# TDA2030_2_1.net
KiCad netlist of a schematic drawn in Altium Designer
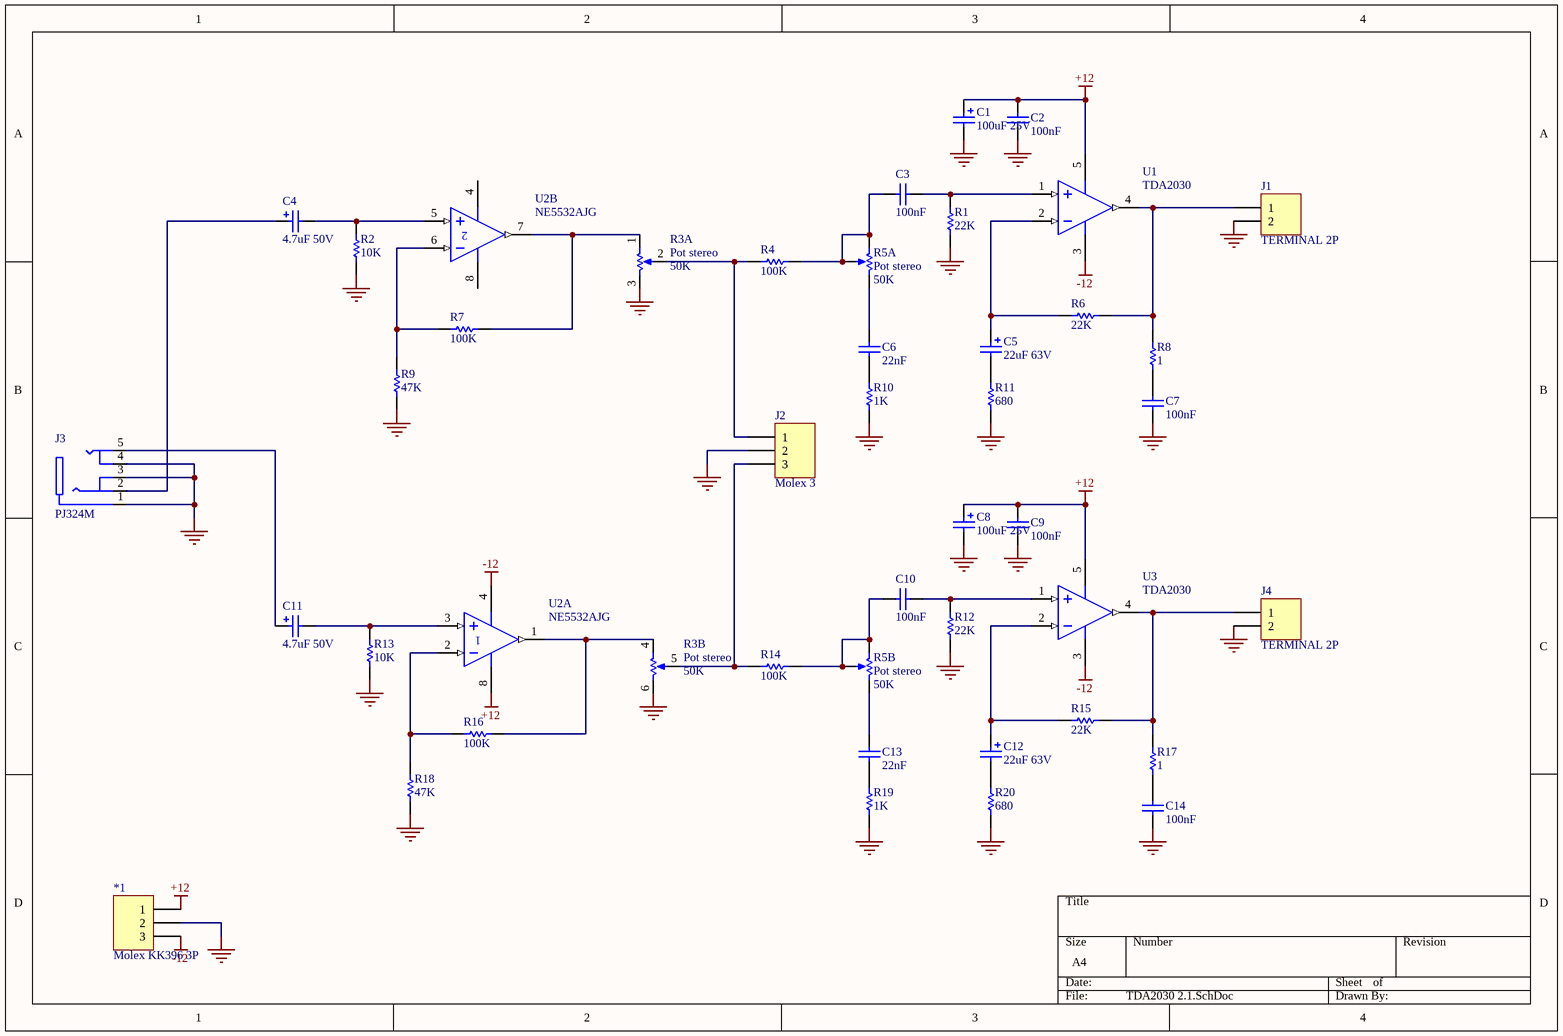
[diagram p0: TDA2030 2.1.SchDoc]

(export (version "E")
  (design (tool "Eeschema 10.0.6"))
  (components
    (comp (ref "*1")
      (value "Molex KK396 3P")
      (footprint "Molex kk396 3P")
      (libsource (lib "Schlib") (part "Molex KK396 3P"))
    )
    (comp (ref "C1")
      (value "100uF 25V")
      (footprint "100uF 25V")
      (description "Polarized Capacitor (Radial)")
      (fields (field (name "PUBLISHER") "Altium Limited"))
      (libsource (lib "Schlib") (part "100uF 25V"))
    )
    (comp (ref "C2")
      (value "100nF")
      (footprint "104")
      (description "Capacitor")
      (fields (field (name "PUBLISHER") "Altium Limited"))
      (libsource (lib "Schlib") (part "104"))
    )
    (comp (ref "C3")
      (value "100nF")
      (footprint "104")
      (description "Capacitor")
      (fields (field (name "PUBLISHER") "Altium Limited"))
      (libsource (lib "Schlib") (part "104"))
    )
    (comp (ref "C4")
      (value "4.7uF 50V")
      (footprint "4.7uF 50V")
      (description "Polarized Capacitor (Radial)")
      (fields (field (name "PUBLISHER") "Altium Limited"))
      (libsource (lib "Schlib") (part "4.7uF 50V"))
    )
    (comp (ref "C5")
      (value "22uF 63V")
      (footprint "22uF 63V")
      (description "Polarized Capacitor (Radial)")
      (fields (field (name "PUBLISHER") "Altium Limited"))
      (libsource (lib "Schlib") (part "22uF 63V"))
    )
    (comp (ref "C6")
      (value "22nF")
      (footprint "104")
      (description "Capacitor")
      (fields (field (name "PUBLISHER") "Altium Limited"))
      (libsource (lib "Schlib") (part "223"))
    )
    (comp (ref "C7")
      (value "100nF")
      (footprint "104")
      (description "Capacitor")
      (fields (field (name "PUBLISHER") "Altium Limited"))
      (libsource (lib "Schlib") (part "104"))
    )
    (comp (ref "C8")
      (value "100uF 25V")
      (footprint "100uF 25V")
      (description "Polarized Capacitor (Radial)")
      (fields (field (name "PUBLISHER") "Altium Limited"))
      (libsource (lib "Schlib") (part "100uF 25V"))
    )
    (comp (ref "C9")
      (value "100nF")
      (footprint "104")
      (description "Capacitor")
      (fields (field (name "PUBLISHER") "Altium Limited"))
      (libsource (lib "Schlib") (part "104"))
    )
    (comp (ref "C10")
      (value "100nF")
      (footprint "104")
      (description "Capacitor")
      (fields (field (name "PUBLISHER") "Altium Limited"))
      (libsource (lib "Schlib") (part "104"))
    )
    (comp (ref "C11")
      (value "4.7uF 50V")
      (footprint "4.7uF 50V")
      (description "Polarized Capacitor (Radial)")
      (fields (field (name "PUBLISHER") "Altium Limited"))
      (libsource (lib "Schlib") (part "4.7uF 50V"))
    )
    (comp (ref "C12")
      (value "22uF 63V")
      (footprint "22uF 63V")
      (description "Polarized Capacitor (Radial)")
      (fields (field (name "PUBLISHER") "Altium Limited"))
      (libsource (lib "Schlib") (part "22uF 63V"))
    )
    (comp (ref "C13")
      (value "22nF")
      (footprint "104")
      (description "Capacitor")
      (fields (field (name "PUBLISHER") "Altium Limited"))
      (libsource (lib "Schlib") (part "223"))
    )
    (comp (ref "C14")
      (value "100nF")
      (footprint "104")
      (description "Capacitor")
      (fields (field (name "PUBLISHER") "Altium Limited"))
      (libsource (lib "Schlib") (part "104"))
    )
    (comp (ref "J1")
      (value "TERMINAL 2P")
      (footprint "TERMINAL 2P")
      (description "Header, 2-Pin")
      (fields (field (name "PUBLISHER") "Altium Limited"))
      (libsource (lib "Schlib") (part "TERMINAL 2P"))
    )
    (comp (ref "J2")
      (value "Molex 3")
      (footprint "Molex kk100 3P")
      (description "Header, 3-Pin")
      (fields (field (name "PUBLISHER") "Altium Limited"))
      (libsource (lib "Schlib") (part "Molex kk100 3P"))
    )
    (comp (ref "J3")
      (value "PJ324M")
      (footprint "WENZHOU_PJ324M")
      (description "Headphone Stereo jack/Audio connector")
      (fields (field (name "MF") "Wenzhou QingPu Electronics Co.Ltd"))
      (libsource (lib "Schlib") (part "PJ324M"))
    )
    (comp (ref "J4")
      (value "TERMINAL 2P")
      (footprint "TERMINAL 2P")
      (description "Header, 2-Pin")
      (fields (field (name "PUBLISHER") "Altium Limited"))
      (libsource (lib "Schlib") (part "TERMINAL 2P"))
    )
    (comp (ref "R1")
      (value "22K")
      (footprint "AXIAL-0.4")
      (description "Resistor")
      (fields (field (name "PUBLISHER") "Altium Limited"))
      (libsource (lib "Miscellaneous Devices") (part "Res1"))
    )
    (comp (ref "R2")
      (value "10K")
      (footprint "AXIAL-0.4")
      (description "Resistor")
      (fields (field (name "PUBLISHER") "Altium Limited"))
      (libsource (lib "Miscellaneous Devices") (part "Res1"))
    )
    (comp (ref "R3")
      (value "Pot stereo")
      (footprint "Pote doble")
      (description "Potentiometer")
      (fields (field (name "ALTIUM_VALUE") "50K") (field (name "PUBLISHER") "Altium Limited"))
      (libsource (lib "") (part "RPot_1"))
    )
    (comp (ref "R4")
      (value "100K")
      (footprint "AXIAL-0.4")
      (description "Resistor")
      (fields (field (name "PUBLISHER") "Altium Limited"))
      (libsource (lib "Miscellaneous Devices") (part "Res1"))
    )
    (comp (ref "R5")
      (value "Pot stereo")
      (footprint "Pote doble")
      (description "Potentiometer")
      (fields (field (name "ALTIUM_VALUE") "50K") (field (name "PUBLISHER") "Altium Limited"))
      (libsource (lib "Schlib") (part "RPot"))
    )
    (comp (ref "R6")
      (value "22K")
      (footprint "AXIAL-0.4")
      (description "Resistor")
      (fields (field (name "PUBLISHER") "Altium Limited"))
      (libsource (lib "Miscellaneous Devices") (part "Res1"))
    )
    (comp (ref "R7")
      (value "100K")
      (footprint "AXIAL-0.4")
      (description "Resistor")
      (fields (field (name "PUBLISHER") "Altium Limited"))
      (libsource (lib "Miscellaneous Devices") (part "Res1"))
    )
    (comp (ref "R8")
      (value "1")
      (footprint "AXIAL-0.4")
      (description "Resistor")
      (fields (field (name "PUBLISHER") "Altium Limited"))
      (libsource (lib "Miscellaneous Devices") (part "Res1"))
    )
    (comp (ref "R9")
      (value "47K")
      (footprint "AXIAL-0.4")
      (description "Resistor")
      (fields (field (name "PUBLISHER") "Altium Limited"))
      (libsource (lib "Miscellaneous Devices") (part "Res1"))
    )
    (comp (ref "R10")
      (value "1K")
      (footprint "AXIAL-0.4")
      (description "Resistor")
      (fields (field (name "PUBLISHER") "Altium Limited"))
      (libsource (lib "Miscellaneous Devices") (part "Res1"))
    )
    (comp (ref "R11")
      (value "680")
      (footprint "AXIAL-0.4")
      (description "Resistor")
      (fields (field (name "PUBLISHER") "Altium Limited"))
      (libsource (lib "Miscellaneous Devices") (part "Res1"))
    )
    (comp (ref "R12")
      (value "22K")
      (footprint "AXIAL-0.4")
      (description "Resistor")
      (fields (field (name "PUBLISHER") "Altium Limited"))
      (libsource (lib "Miscellaneous Devices") (part "Res1"))
    )
    (comp (ref "R13")
      (value "10K")
      (footprint "AXIAL-0.4")
      (description "Resistor")
      (fields (field (name "PUBLISHER") "Altium Limited"))
      (libsource (lib "Miscellaneous Devices") (part "Res1"))
    )
    (comp (ref "R14")
      (value "100K")
      (footprint "AXIAL-0.4")
      (description "Resistor")
      (fields (field (name "PUBLISHER") "Altium Limited"))
      (libsource (lib "Miscellaneous Devices") (part "Res1"))
    )
    (comp (ref "R15")
      (value "22K")
      (footprint "AXIAL-0.4")
      (description "Resistor")
      (fields (field (name "PUBLISHER") "Altium Limited"))
      (libsource (lib "Miscellaneous Devices") (part "Res1"))
    )
    (comp (ref "R16")
      (value "100K")
      (footprint "AXIAL-0.4")
      (description "Resistor")
      (fields (field (name "PUBLISHER") "Altium Limited"))
      (libsource (lib "Miscellaneous Devices") (part "Res1"))
    )
    (comp (ref "R17")
      (value "1")
      (footprint "AXIAL-0.4")
      (description "Resistor")
      (fields (field (name "PUBLISHER") "Altium Limited"))
      (libsource (lib "Miscellaneous Devices") (part "Res1"))
    )
    (comp (ref "R18")
      (value "47K")
      (footprint "AXIAL-0.4")
      (description "Resistor")
      (fields (field (name "PUBLISHER") "Altium Limited"))
      (libsource (lib "Miscellaneous Devices") (part "Res1"))
    )
    (comp (ref "R19")
      (value "1K")
      (footprint "AXIAL-0.4 MIA")
      (description "Resistor")
      (fields (field (name "PUBLISHER") "Altium Limited"))
      (libsource (lib "Miscellaneous Devices") (part "Res1"))
    )
    (comp (ref "R20")
      (value "680")
      (footprint "AXIAL-0.4")
      (description "Resistor")
      (fields (field (name "PUBLISHER") "Altium Limited"))
      (libsource (lib "Miscellaneous Devices") (part "Res1"))
    )
    (comp (ref "U1") (value "TDA2030") (footprint "TDA2030") (libsource (lib "Schlib") (part "TDA2030")))
    (comp (ref "U2")
      (value "NE5532AJG")
      (footprint "DIP-8")
      (description "Dual Low-Noise Operational Amplifier")
      (fields (field (name "PUBLISHER") "Altium Limited"))
      (libsource (lib "TI Operational Amplifier") (part "NE5532AJG"))
    )
    (comp (ref "U3") (value "TDA2030") (footprint "TDA2030") (libsource (lib "Schlib") (part "TDA2030")))
  )
  (nets
    (net (code "1") (name "+12") (class "Default")
      (node (ref "*1") (pin "1") (pinfunction "1_1") (pintype "passive"))
      (node (ref "C1") (pin "1") (pinfunction "1_1") (pintype "passive"))
      (node (ref "C2") (pin "2") (pinfunction "2_2") (pintype "passive"))
      (node (ref "C8") (pin "1") (pinfunction "1_1") (pintype "passive"))
      (node (ref "C9") (pin "1") (pinfunction "1_1") (pintype "passive"))
      (node (ref "U1") (pin "5") (pinfunction "V+_5") (pintype "power_in"))
      (node (ref "U2") (pin "8") (pinfunction "V+_8") (pintype "power_in"))
      (node (ref "U3") (pin "5") (pinfunction "V+_5") (pintype "power_in"))
    )
    (net (code "2") (name "-12") (class "Default")
      (node (ref "*1") (pin "3") (pinfunction "3_3") (pintype "passive"))
      (node (ref "U1") (pin "3") (pinfunction "V-_3") (pintype "power_in"))
      (node (ref "U2") (pin "4") (pinfunction "V-_4") (pintype "power_in"))
      (node (ref "U3") (pin "3") (pinfunction "V-_3") (pintype "power_in"))
    )
    (net (code "3") (name "GND") (class "Default")
      (node (ref "*1") (pin "2") (pinfunction "2_2") (pintype "passive"))
      (node (ref "C1") (pin "2") (pinfunction "2_2") (pintype "passive"))
      (node (ref "C14") (pin "2") (pinfunction "2_2") (pintype "passive"))
      (node (ref "C2") (pin "1") (pinfunction "1_1") (pintype "passive"))
      (node (ref "C7") (pin "2") (pinfunction "2_2") (pintype "passive"))
      (node (ref "C8") (pin "2") (pinfunction "2_2") (pintype "passive"))
      (node (ref "C9") (pin "2") (pinfunction "2_2") (pintype "passive"))
      (node (ref "J1") (pin "2") (pinfunction "2_2") (pintype "passive"))
      (node (ref "J2") (pin "2") (pinfunction "2_2") (pintype "passive"))
      (node (ref "J3") (pin "1") (pinfunction "SLEEVE_1") (pintype "passive"))
      (node (ref "J3") (pin "3") (pinfunction "RING_2_3") (pintype "passive"))
      (node (ref "J3") (pin "4") (pinfunction "TIP_1_4") (pintype "passive"))
      (node (ref "J4") (pin "2") (pinfunction "2_2") (pintype "passive"))
      (node (ref "R1") (pin "1") (pinfunction "1_1") (pintype "passive"))
      (node (ref "R10") (pin "2") (pinfunction "2_2") (pintype "passive"))
      (node (ref "R11") (pin "1") (pinfunction "1_1") (pintype "passive"))
      (node (ref "R12") (pin "1") (pinfunction "1_1") (pintype "passive"))
      (node (ref "R13") (pin "2") (pinfunction "2_2") (pintype "passive"))
      (node (ref "R18") (pin "2") (pinfunction "2_2") (pintype "passive"))
      (node (ref "R19") (pin "2") (pinfunction "2_2") (pintype "passive"))
      (node (ref "R2") (pin "2") (pinfunction "2_2") (pintype "passive"))
      (node (ref "R20") (pin "1") (pinfunction "1_1") (pintype "passive"))
      (node (ref "R3") (pin "3") (pinfunction "BOT_3") (pintype "passive"))
      (node (ref "R3") (pin "6") (pinfunction "BOT_6") (pintype "passive"))
      (node (ref "R9") (pin "2") (pinfunction "2_2") (pintype "passive"))
    )
    (net (code "4") (name "Net-(C5-Pad2)") (class "Default")
      (node (ref "C5") (pin "2") (pinfunction "2_2") (pintype "passive"))
      (node (ref "R11") (pin "2") (pinfunction "2_2") (pintype "passive"))
    )
    (net (code "5") (name "Net-(C6-Pad1)") (class "Default")
      (node (ref "C6") (pin "1") (pinfunction "1_1") (pintype "passive"))
      (node (ref "R10") (pin "1") (pinfunction "1_1") (pintype "passive"))
    )
    (net (code "6") (name "Net-(C7-Pad1)") (class "Default")
      (node (ref "C7") (pin "1") (pinfunction "1_1") (pintype "passive"))
      (node (ref "R8") (pin "2") (pinfunction "2_2") (pintype "passive"))
    )
    (net (code "7") (name "Net-(C12-Pad2)") (class "Default")
      (node (ref "C12") (pin "2") (pinfunction "2_2") (pintype "passive"))
      (node (ref "R20") (pin "2") (pinfunction "2_2") (pintype "passive"))
    )
    (net (code "8") (name "Net-(C13-Pad1)") (class "Default")
      (node (ref "C13") (pin "1") (pinfunction "1_1") (pintype "passive"))
      (node (ref "R19") (pin "1") (pinfunction "1_1") (pintype "passive"))
    )
    (net (code "9") (name "Net-(C14-Pad1)") (class "Default")
      (node (ref "C14") (pin "1") (pinfunction "1_1") (pintype "passive"))
      (node (ref "R17") (pin "2") (pinfunction "2_2") (pintype "passive"))
    )
    (net (code "10") (name "Net-(J3-RING_1)") (class "Default")
      (node (ref "C4") (pin "1") (pinfunction "1_1") (pintype "passive"))
      (node (ref "J3") (pin "2") (pinfunction "RING_1_2") (pintype "passive"))
    )
    (net (code "11") (name "Net-(J3-TIP_2)") (class "Default")
      (node (ref "C11") (pin "1") (pinfunction "1_1") (pintype "passive"))
      (node (ref "J3") (pin "5") (pinfunction "TIP_2_5") (pintype "passive"))
    )
    (net (code "12") (name "Net-(R3A-TAP)") (class "Default")
      (node (ref "J2") (pin "1") (pinfunction "1_1") (pintype "passive"))
      (node (ref "R3") (pin "2") (pinfunction "TAP_2") (pintype "passive"))
      (node (ref "R4") (pin "2") (pinfunction "2_2") (pintype "passive"))
    )
    (net (code "13") (name "Net-(R3A-TOP)") (class "Default")
      (node (ref "R3") (pin "1") (pinfunction "TOP_1") (pintype "passive"))
      (node (ref "R7") (pin "1") (pinfunction "1_1") (pintype "passive"))
      (node (ref "U2") (pin "7") (pinfunction "OUT_7") (pintype "output"))
    )
    (net (code "14") (name "Net-(R3B-TAP)") (class "Default")
      (node (ref "J2") (pin "3") (pinfunction "3_3") (pintype "passive"))
      (node (ref "R14") (pin "2") (pinfunction "2_2") (pintype "passive"))
      (node (ref "R3") (pin "5") (pinfunction "TAP_5") (pintype "passive"))
    )
    (net (code "15") (name "Net-(R3B-TOP)") (class "Default")
      (node (ref "R16") (pin "1") (pinfunction "1_1") (pintype "passive"))
      (node (ref "R3") (pin "4") (pinfunction "TOP_4") (pintype "passive"))
      (node (ref "U2") (pin "1") (pinfunction "OUT_1") (pintype "output"))
    )
    (net (code "16") (name "Net-(R5A-BOT)") (class "Default")
      (node (ref "C3") (pin "2") (pinfunction "2_2") (pintype "passive"))
      (node (ref "R4") (pin "1") (pinfunction "1_1") (pintype "passive"))
      (node (ref "R5") (pin "2") (pinfunction "TAP_2") (pintype "passive"))
      (node (ref "R5") (pin "3") (pinfunction "BOT_3") (pintype "passive"))
    )
    (net (code "17") (name "Net-(R5A-TOP)") (class "Default")
      (node (ref "C6") (pin "2") (pinfunction "2_2") (pintype "passive"))
      (node (ref "R5") (pin "1") (pinfunction "TOP_1") (pintype "passive"))
    )
    (net (code "18") (name "Net-(R5B-BOT)") (class "Default")
      (node (ref "C10") (pin "2") (pinfunction "2_2") (pintype "passive"))
      (node (ref "R14") (pin "1") (pinfunction "1_1") (pintype "passive"))
      (node (ref "R5") (pin "5") (pinfunction "TAP_5") (pintype "passive"))
      (node (ref "R5") (pin "6") (pinfunction "BOT_6") (pintype "passive"))
    )
    (net (code "19") (name "Net-(R5B-TOP)") (class "Default")
      (node (ref "C13") (pin "2") (pinfunction "2_2") (pintype "passive"))
      (node (ref "R5") (pin "4") (pinfunction "TOP_4") (pintype "passive"))
    )
    (net (code "20") (name "Net-(U1-IN+)") (class "Default")
      (node (ref "C3") (pin "1") (pinfunction "1_1") (pintype "passive"))
      (node (ref "R1") (pin "2") (pinfunction "2_2") (pintype "passive"))
      (node (ref "U1") (pin "1") (pinfunction "IN+_1") (pintype "input"))
    )
    (net (code "21") (name "Net-(U1-IN-)") (class "Default")
      (node (ref "C5") (pin "1") (pinfunction "1_1") (pintype "passive"))
      (node (ref "R6") (pin "2") (pinfunction "2_2") (pintype "passive"))
      (node (ref "U1") (pin "2") (pinfunction "IN-_2") (pintype "input"))
    )
    (net (code "22") (name "Net-(U1-OUT)") (class "Default")
      (node (ref "J1") (pin "1") (pinfunction "1_1") (pintype "passive"))
      (node (ref "R6") (pin "1") (pinfunction "1_1") (pintype "passive"))
      (node (ref "R8") (pin "1") (pinfunction "1_1") (pintype "passive"))
      (node (ref "U1") (pin "4") (pinfunction "OUT_4") (pintype "output"))
    )
    (net (code "23") (name "Net-(U2A-IN+)") (class "Default")
      (node (ref "C11") (pin "2") (pinfunction "2_2") (pintype "passive"))
      (node (ref "R13") (pin "1") (pinfunction "1_1") (pintype "passive"))
      (node (ref "U2") (pin "3") (pinfunction "IN+_3") (pintype "input"))
    )
    (net (code "24") (name "Net-(U2A-IN-)") (class "Default")
      (node (ref "R16") (pin "2") (pinfunction "2_2") (pintype "passive"))
      (node (ref "R18") (pin "1") (pinfunction "1_1") (pintype "passive"))
      (node (ref "U2") (pin "2") (pinfunction "IN-_2") (pintype "input"))
    )
    (net (code "25") (name "Net-(U2B-IN+)") (class "Default")
      (node (ref "C4") (pin "2") (pinfunction "2_2") (pintype "passive"))
      (node (ref "R2") (pin "1") (pinfunction "1_1") (pintype "passive"))
      (node (ref "U2") (pin "5") (pinfunction "IN+_5") (pintype "input"))
    )
    (net (code "26") (name "Net-(U2B-IN-)") (class "Default")
      (node (ref "R7") (pin "2") (pinfunction "2_2") (pintype "passive"))
      (node (ref "R9") (pin "1") (pinfunction "1_1") (pintype "passive"))
      (node (ref "U2") (pin "6") (pinfunction "IN-_6") (pintype "input"))
    )
    (net (code "27") (name "Net-(U3-IN+)") (class "Default")
      (node (ref "C10") (pin "1") (pinfunction "1_1") (pintype "passive"))
      (node (ref "R12") (pin "2") (pinfunction "2_2") (pintype "passive"))
      (node (ref "U3") (pin "1") (pinfunction "IN+_1") (pintype "input"))
    )
    (net (code "28") (name "Net-(U3-IN-)") (class "Default")
      (node (ref "C12") (pin "1") (pinfunction "1_1") (pintype "passive"))
      (node (ref "R15") (pin "2") (pinfunction "2_2") (pintype "passive"))
      (node (ref "U3") (pin "2") (pinfunction "IN-_2") (pintype "input"))
    )
    (net (code "29") (name "Net-(U3-OUT)") (class "Default")
      (node (ref "J4") (pin "1") (pinfunction "1_1") (pintype "passive"))
      (node (ref "R15") (pin "1") (pinfunction "1_1") (pintype "passive"))
      (node (ref "R17") (pin "1") (pinfunction "1_1") (pintype "passive"))
      (node (ref "U3") (pin "4") (pinfunction "OUT_4") (pintype "output"))
    )
    (net (code "30") (name "unconnected-(U2B-V+-Pad8)") (class "Default")
      (node (ref "U2") (pin "8") (pinfunction "V+_8") (pintype "power_in"))
    )
    (net (code "31") (name "unconnected-(U2B-V--Pad4)") (class "Default")
      (node (ref "U2") (pin "4") (pinfunction "V-_4") (pintype "power_in"))
    )
  )
)
